# camera.net
KiCad netlist of a schematic drawn in Altium Designer
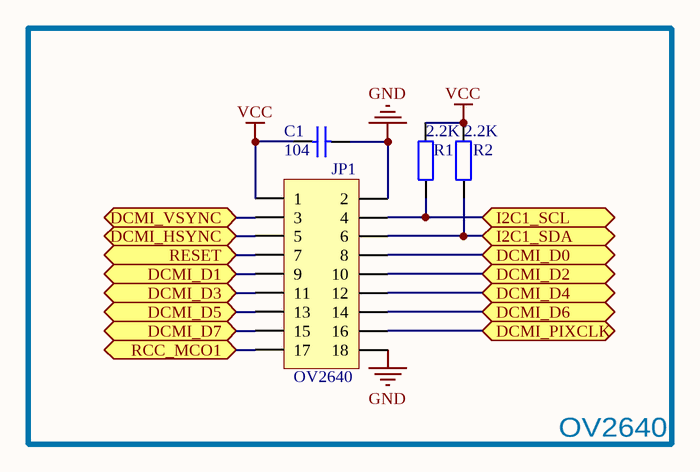
[diagram p0: camera.SchDoc]

(export (version "E")
  (design (tool "Eeschema 10.0.6"))
  (components
    (comp (ref "C1")
      (value "104")
      (footprint "C 0603_L")
      (description "Capacitor")
      (fields (field (name "PUBLISHER") "Altium Limited"))
      (libsource (lib "Miscellaneous Devices") (part "Cap"))
    )
    (comp (ref "JP1")
      (value "OV2640")
      (footprint "HDR2.54-LI-2x9P")
      (description "9*2P接插件")
      (fields (field (name "版权归属") "源创客"))
      (libsource (lib "4.5   - 接插件-脚距2.54") (part "Header 9X2"))
    )
    (comp (ref "R1")
      (value "2.2K")
      (footprint "R 0603_L")
      (description "Resistor")
      (fields (field (name "PUBLISHER") "Altium Limited"))
      (libsource (lib "Miscellaneous Devices") (part "Res2"))
    )
    (comp (ref "R2")
      (value "2.2K")
      (footprint "R 0603_L")
      (description "Resistor")
      (fields (field (name "PUBLISHER") "Altium Limited"))
      (libsource (lib "Miscellaneous Devices") (part "Res2"))
    )
  )
  (nets
    (net (code "1") (name "/DCMI_D0") (class "Default")
      (node (ref "JP1") (pin "8") (pinfunction "8_8") (pintype "passive"))
    )
    (net (code "2") (name "/DCMI_D1") (class "Default")
      (node (ref "JP1") (pin "9") (pinfunction "9_9") (pintype "passive"))
    )
    (net (code "3") (name "/DCMI_D2") (class "Default")
      (node (ref "JP1") (pin "10") (pinfunction "10_10") (pintype "passive"))
    )
    (net (code "4") (name "/DCMI_D3") (class "Default")
      (node (ref "JP1") (pin "11") (pinfunction "11_11") (pintype "passive"))
    )
    (net (code "5") (name "/DCMI_D4") (class "Default")
      (node (ref "JP1") (pin "12") (pinfunction "12_12") (pintype "passive"))
    )
    (net (code "6") (name "/DCMI_D5") (class "Default")
      (node (ref "JP1") (pin "13") (pinfunction "13_13") (pintype "passive"))
    )
    (net (code "7") (name "/DCMI_D6") (class "Default")
      (node (ref "JP1") (pin "14") (pinfunction "14_14") (pintype "passive"))
    )
    (net (code "8") (name "/DCMI_D7") (class "Default")
      (node (ref "JP1") (pin "15") (pinfunction "15_15") (pintype "passive"))
    )
    (net (code "9") (name "/DCMI_HSYNC") (class "Default")
      (node (ref "JP1") (pin "5") (pinfunction "5_5") (pintype "passive"))
    )
    (net (code "10") (name "/DCMI_PIXCLK") (class "Default")
      (node (ref "JP1") (pin "16") (pinfunction "16_16") (pintype "passive"))
    )
    (net (code "11") (name "/DCMI_VSYNC") (class "Default")
      (node (ref "JP1") (pin "3") (pinfunction "3_3") (pintype "passive"))
    )
    (net (code "12") (name "/I2C1_SCL") (class "Default")
      (node (ref "JP1") (pin "4") (pinfunction "4_4") (pintype "passive"))
      (node (ref "R1") (pin "1") (pinfunction "1_1") (pintype "passive"))
    )
    (net (code "13") (name "/I2C1_SDA") (class "Default")
      (node (ref "JP1") (pin "6") (pinfunction "6_6") (pintype "passive"))
      (node (ref "R2") (pin "1") (pinfunction "1_1") (pintype "passive"))
    )
    (net (code "14") (name "/RCC_MCO1") (class "Default")
      (node (ref "JP1") (pin "17") (pinfunction "17_17") (pintype "passive"))
    )
    (net (code "15") (name "/RESET") (class "Default")
      (node (ref "JP1") (pin "7") (pinfunction "7_7") (pintype "passive"))
    )
    (net (code "16") (name "GND") (class "Default")
      (node (ref "C1") (pin "1") (pinfunction "1_1") (pintype "passive"))
      (node (ref "JP1") (pin "18") (pinfunction "18_18") (pintype "passive"))
      (node (ref "JP1") (pin "2") (pinfunction "2_2") (pintype "passive"))
    )
    (net (code "17") (name "VCC") (class "Default")
      (node (ref "C1") (pin "2") (pinfunction "2_2") (pintype "passive"))
      (node (ref "JP1") (pin "1") (pinfunction "1_1") (pintype "passive"))
      (node (ref "R1") (pin "2") (pinfunction "2_2") (pintype "passive"))
      (node (ref "R2") (pin "2") (pinfunction "2_2") (pintype "passive"))
    )
  )
)
